# 5v_Reg_biggr.net
KiCad netlist of a schematic drawn in Altium Designer
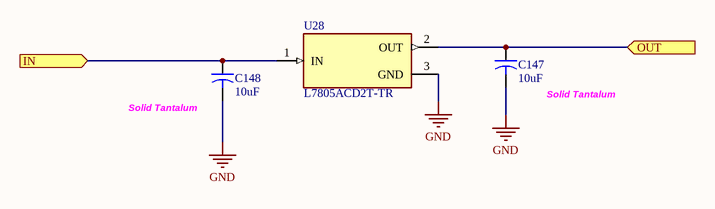
[diagram p0: 5v_Reg_biggr.SchDoc]

(export (version "E")
  (design (tool "Eeschema 10.0.6"))
  (components
    (comp (ref "C147")
      (value "10uF")
      (footprint "Tantalum_2917")
      (description "Capacitor, 100uF NICHICON")
      (libsource (lib "Arturo_Approved") (part "UVR1V102MHD1TO"))
    )
    (comp (ref "C148")
      (value "10uF")
      (footprint "Tantalum_2917")
      (description "Capacitor, 100uF NICHICON")
      (libsource (lib "Arturo_Approved") (part "UVR1V102MHD1TO"))
    )
    (comp (ref "U28")
      (value "L7805ACD2T-TR")
      (footprint "Arturo_Approved:TO254P1515X470-3N")
      (description "Linear Voltage Regulator IC 1 Output 1.5A D2PAK")
      (fields (field (name "MF") "STMicroelectronics"))
      (libsource (lib "Arturo_Approved") (part "L7805ACD2T-TR"))
    )
  )
  (nets
    (net (code "1") (name "/IN") (class "Default")
      (node (ref "C148") (pin "1") (pinfunction "1_1") (pintype "passive"))
      (node (ref "U28") (pin "1") (pinfunction "IN_1") (pintype "input"))
    )
    (net (code "2") (name "/OUT") (class "Default")
      (node (ref "C147") (pin "1") (pinfunction "1_1") (pintype "passive"))
      (node (ref "U28") (pin "2") (pinfunction "OUT_2") (pintype "output"))
    )
    (net (code "3") (name "GND") (class "Default")
      (node (ref "C147") (pin "2") (pinfunction "2_2") (pintype "passive"))
      (node (ref "C148") (pin "2") (pinfunction "2_2") (pintype "passive"))
      (node (ref "U28") (pin "3") (pinfunction "GND_3") (pintype "power_in"))
    )
  )
)
